# Printhead2.net
KiCad netlist of a schematic drawn in Altium Designer
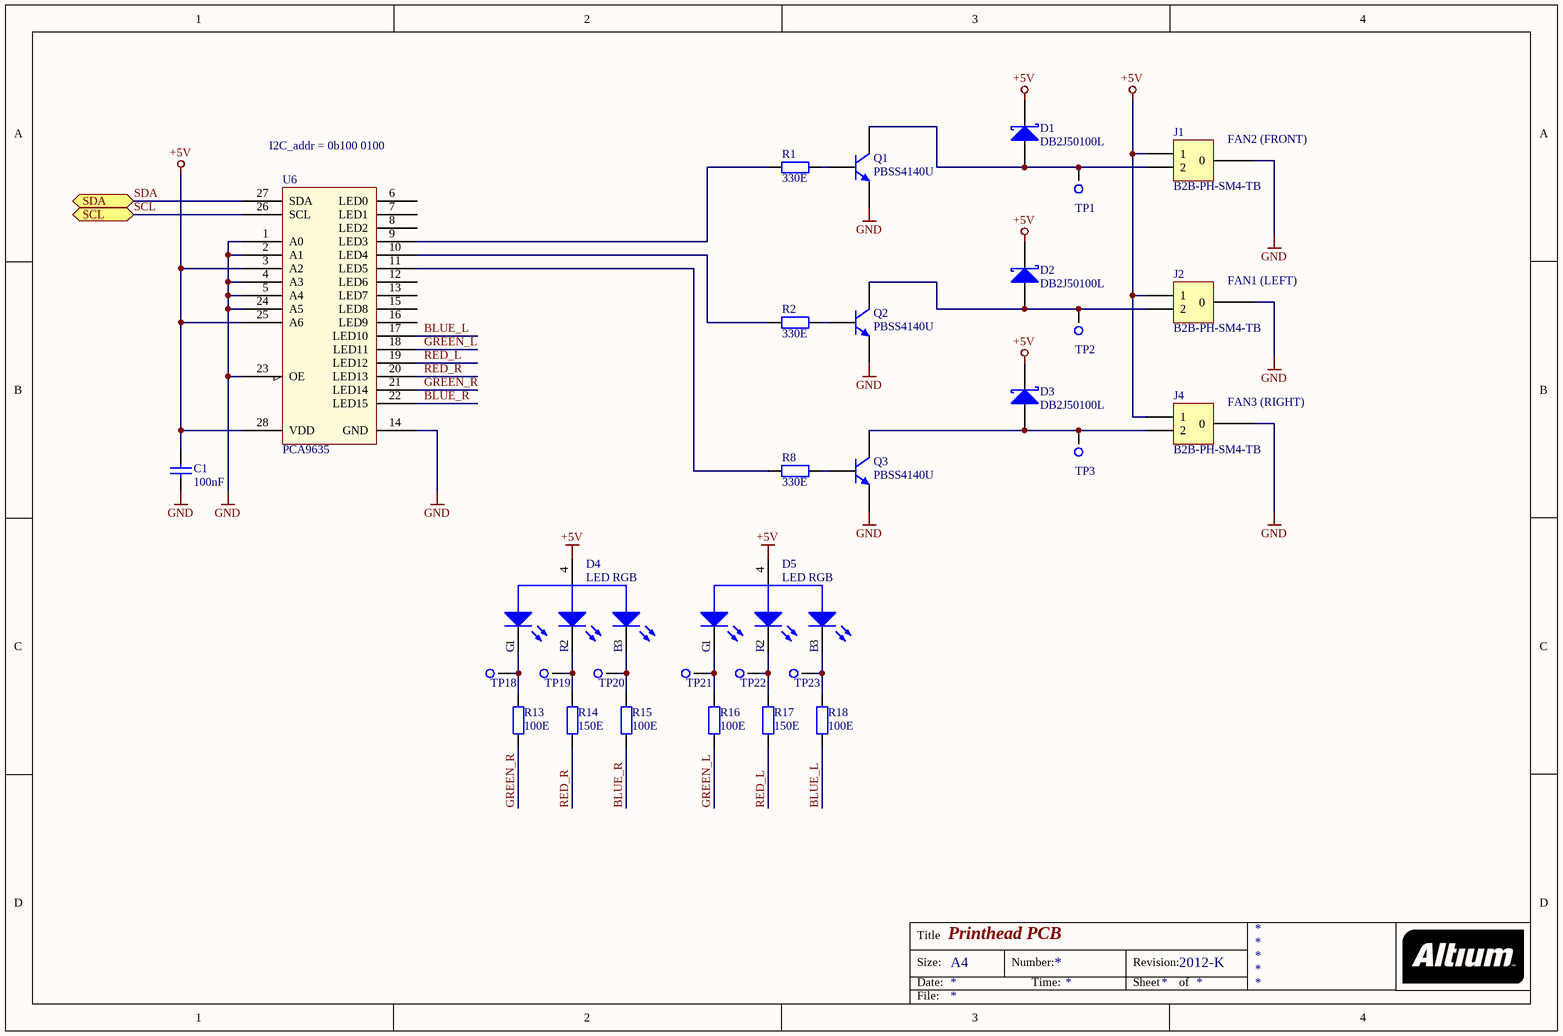
[diagram p0: Printhead2.SchDoc]

(export (version "E")
  (design (tool "Eeschema 10.0.6"))
  (components
    (comp (ref "C1")
      (value "100nF")
      (footprint "CAPC1608X09N")
      (description "CAP CER 0.1UF 50V 10% X7R 0603")
      (fields
        (field (name "MANUFACTURER") "Yageo")
        (field (name "MANUFACTURER PART NUMBER") "CC0603KRX7R9BB104")
      )
      (libsource (lib "Marlin") (part "100nF/50V/0603"))
    )
    (comp (ref "D1")
      (value "DB2J50100L")
      (footprint "SODFL2512X80N")
      (description "DIODE SCHOTTKY 50V 200MA MINI2")
      (fields (field (name "MANUFACTURER") "Panasonic Electronic Components - Semiconductor Products"))
      (libsource (lib "Marlin") (part "DB2J50100L"))
    )
    (comp (ref "D2")
      (value "DB2J50100L")
      (footprint "SODFL2512X80N")
      (description "DIODE SCHOTTKY 50V 200MA MINI2")
      (fields (field (name "MANUFACTURER") "Panasonic Electronic Components - Semiconductor Products"))
      (libsource (lib "Marlin") (part "DB2J50100L"))
    )
    (comp (ref "D3")
      (value "DB2J50100L")
      (footprint "SODFL2512X80N")
      (description "DIODE SCHOTTKY 50V 200MA MINI2")
      (fields (field (name "MANUFACTURER") "Panasonic Electronic Components - Semiconductor Products"))
      (libsource (lib "Marlin") (part "DB2J50100L"))
    )
    (comp (ref "D4")
      (value "LED RGB")
      (footprint "Dialight 598-8610-307F")
      (description "LED MULTICOLOR RED/GRN/BLUE")
      (fields (field (name "MFG") "Dialight") (field (name "MANUFACTURER PART NUMBER") "598-8610-307F"))
      (libsource (lib "Faber_SCH_lib") (part "LED 598-8810-307F"))
    )
    (comp (ref "D5")
      (value "LED RGB")
      (footprint "Dialight 598-8610-307F")
      (description "LED MULTICOLOR RED/GRN/BLUE")
      (fields (field (name "MFG") "Dialight") (field (name "MANUFACTURER PART NUMBER") "598-8610-307F"))
      (libsource (lib "Faber_SCH_lib") (part "LED 598-8810-307F"))
    )
    (comp (ref "J1")
      (value "B2B-PH-SM4-TB")
      (footprint "B2B-PH-SM4-TB")
      (description "JST B2B-PH-SM4-TB")
      (fields (field (name "MFG") "JST"))
      (libsource (lib "printehead") (part "Header 2"))
    )
    (comp (ref "J2")
      (value "B2B-PH-SM4-TB")
      (footprint "B2B-PH-SM4-TB")
      (description "JST B2B-PH-SM4-TB")
      (fields (field (name "MFG") "JST"))
      (libsource (lib "printehead") (part "Header 2"))
    )
    (comp (ref "J4")
      (value "B2B-PH-SM4-TB")
      (footprint "B2B-PH-SM4-TB")
      (description "JST B2B-PH-SM4-TB")
      (fields (field (name "MFG") "JST"))
      (libsource (lib "printehead") (part "Header 2"))
    )
    (comp (ref "Q1")
      (value "PBSS4140U")
      (footprint "SOT65P210X110-3N")
      (description "TRANS NPN 40V 1000MA SOT323")
      (fields
        (field (name "MANUFACTURER") "NXP Semiconductors")
        (field (name "MANUFACTURER PART NUMBER") "PBSS4140U,115")
      )
      (libsource (lib "Marlin") (part "PBSS4140U"))
    )
    (comp (ref "Q2")
      (value "PBSS4140U")
      (footprint "SOT65P210X110-3N")
      (description "TRANS NPN 40V 1000MA SOT323")
      (fields
        (field (name "MANUFACTURER") "NXP Semiconductors")
        (field (name "MANUFACTURER PART NUMBER") "PBSS4140U,115")
      )
      (libsource (lib "Marlin") (part "PBSS4140U"))
    )
    (comp (ref "Q3")
      (value "PBSS4140U")
      (footprint "SOT65P210X110-3N")
      (description "TRANS NPN 40V 1000MA SOT323")
      (fields
        (field (name "MANUFACTURER") "NXP Semiconductors")
        (field (name "MANUFACTURER PART NUMBER") "PBSS4140U,115")
      )
      (libsource (lib "Marlin") (part "PBSS4140U"))
    )
    (comp (ref "R1")
      (value "330E")
      (footprint "ulticontroller2:RESC1608X05N")
      (description "RES 330 OHM 1/10W 1% 0603 SMD")
      (fields
        (field (name "MANUFACTURER") "Vishay Dale")
        (field (name "MANUFACTURER PART NUMBER") "CRCW0603330RFKEA")
      )
      (libsource (lib "Marlin") (part "330E/0603"))
    )
    (comp (ref "R2")
      (value "330E")
      (footprint "RESC1608X05N")
      (description "RES 330 OHM 1/10W 1% 0603 SMD")
      (fields
        (field (name "MANUFACTURER") "Vishay Dale")
        (field (name "MANUFACTURER PART NUMBER") "CRCW0603330RFKEA")
      )
      (libsource (lib "Marlin") (part "330E/0603"))
    )
    (comp (ref "R8")
      (value "330E")
      (footprint "RESC1608X05N")
      (description "RES 330 OHM 1/10W 1% 0603 SMD")
      (fields
        (field (name "MANUFACTURER") "Vishay Dale")
        (field (name "MANUFACTURER PART NUMBER") "CRCW0603330RFKEA")
      )
      (libsource (lib "Marlin") (part "330E/0603"))
    )
    (comp (ref "R13")
      (value "100E")
      (footprint "R0805 (2012)")
      (description "Res 100E 0805 1% 125mW")
      (fields
        (field (name "MFG") "YAGEO")
        (field (name "MANUFACTURER PART NUMBER") "WRC31022/ RC0805FR-07100RL")
      )
      (libsource (lib "Faber_SCH_lib") (part "Res 100E 0805"))
    )
    (comp (ref "R14")
      (value "150E")
      (footprint "R0805 (2012)")
      (description "Res 150E 0805 1% 125mW")
      (fields (field (name "MFG") "YAGEO") (field (name "MANUFACTURER PART NUMBER") "2322 734 61501"))
      (libsource (lib "Faber_SCH_lib") (part "Res 150E 0805"))
    )
    (comp (ref "R15")
      (value "100E")
      (footprint "R0805 (2012)")
      (description "Res 100E 0805 1% 125mW")
      (fields
        (field (name "MFG") "YAGEO")
        (field (name "MANUFACTURER PART NUMBER") "WRC31022/ RC0805FR-07100RL")
      )
      (libsource (lib "Faber_SCH_lib") (part "Res 100E 0805"))
    )
    (comp (ref "R16")
      (value "100E")
      (footprint "R0805 (2012)")
      (description "Res 100E 0805 1% 125mW")
      (fields
        (field (name "MFG") "YAGEO")
        (field (name "MANUFACTURER PART NUMBER") "WRC31022/ RC0805FR-07100RL")
      )
      (libsource (lib "Faber_SCH_lib") (part "Res 100E 0805"))
    )
    (comp (ref "R17")
      (value "150E")
      (footprint "R0805 (2012)")
      (description "Res 150E 0805 1% 125mW")
      (fields (field (name "MFG") "YAGEO") (field (name "MANUFACTURER PART NUMBER") "2322 734 61501"))
      (libsource (lib "Faber_SCH_lib") (part "Res 150E 0805"))
    )
    (comp (ref "R18")
      (value "100E")
      (footprint "R0805 (2012)")
      (description "Res 100E 0805 1% 125mW")
      (fields
        (field (name "MFG") "YAGEO")
        (field (name "MANUFACTURER PART NUMBER") "WRC31022/ RC0805FR-07100RL")
      )
      (libsource (lib "Faber_SCH_lib") (part "Res 100E 0805"))
    )
    (comp (ref "TP1")
      (value "Testpoint 1.6mm")
      (footprint "Testpoint 1.6mm")
      (libsource (lib "Ultimaker") (part "Testpoint 1.6mm"))
    )
    (comp (ref "TP2")
      (value "Testpoint 1.6mm")
      (footprint "Testpoint 1.6mm")
      (libsource (lib "Ultimaker") (part "Testpoint 1.6mm"))
    )
    (comp (ref "TP3")
      (value "Testpoint 1.6mm")
      (footprint "Testpoint 1.6mm")
      (libsource (lib "Ultimaker") (part "Testpoint 1.6mm"))
    )
    (comp (ref "TP18")
      (value "Testpoint 1.6mm")
      (footprint "Testpoint 1.6mm")
      (libsource (lib "Ultimaker") (part "Testpoint 1.6mm"))
    )
    (comp (ref "TP19")
      (value "Testpoint 1.6mm")
      (footprint "Testpoint 1.6mm")
      (libsource (lib "Ultimaker") (part "Testpoint 1.6mm"))
    )
    (comp (ref "TP20")
      (value "Testpoint 1.6mm")
      (footprint "Testpoint 1.6mm")
      (libsource (lib "Ultimaker") (part "Testpoint 1.6mm"))
    )
    (comp (ref "TP21")
      (value "Testpoint 1.6mm")
      (footprint "Testpoint 1.6mm")
      (libsource (lib "Ultimaker") (part "Testpoint 1.6mm"))
    )
    (comp (ref "TP22")
      (value "Testpoint 1.6mm")
      (footprint "Testpoint 1.6mm")
      (libsource (lib "Ultimaker") (part "Testpoint 1.6mm"))
    )
    (comp (ref "TP23")
      (value "Testpoint 1.6mm")
      (footprint "Testpoint 1.6mm")
      (libsource (lib "Ultimaker") (part "Testpoint 1.6mm"))
    )
    (comp (ref "U6")
      (value "PCA9635")
      (footprint "TSOP65P640X110-28N")
      (description "16-bit Fm+ I2C-bus LED driver")
      (fields (field (name "MFG") "NXP") (field (name "MANUFACTURER PART NUMBER") "PCA9635PW"))
      (libsource (lib "printehead") (part "PCA9635"))
    )
  )
  (nets
    (net (code "1") (name "+5V") (class "Default")
      (node (ref "C1") (pin "2") (pinfunction "2_2") (pintype "passive"))
      (node (ref "D1") (pin "1") (pinfunction "K_1") (pintype "passive"))
      (node (ref "D2") (pin "1") (pinfunction "K_1") (pintype "passive"))
      (node (ref "D3") (pin "1") (pinfunction "K_1") (pintype "passive"))
      (node (ref "D4") (pin "4") (pinfunction "4_4") (pintype "passive"))
      (node (ref "D5") (pin "4") (pinfunction "4_4") (pintype "passive"))
      (node (ref "J1") (pin "1") (pinfunction "1_1") (pintype "passive"))
      (node (ref "J2") (pin "1") (pinfunction "1_1") (pintype "passive"))
      (node (ref "J4") (pin "1") (pinfunction "1_1") (pintype "passive"))
      (node (ref "U6") (pin "25") (pinfunction "A6_25") (pintype "passive"))
      (node (ref "U6") (pin "28") (pinfunction "VDD_28") (pintype "power_in"))
      (node (ref "U6") (pin "3") (pinfunction "A2_3") (pintype "passive"))
    )
    (net (code "2") (name "/BLUE_L") (class "Default")
      (node (ref "R18") (pin "1") (pinfunction "1_1") (pintype "passive"))
      (node (ref "U6") (pin "17") (pinfunction "LED10_17") (pintype "passive"))
    )
    (net (code "3") (name "/BLUE_R") (class "Default")
      (node (ref "R15") (pin "1") (pinfunction "1_1") (pintype "passive"))
      (node (ref "U6") (pin "22") (pinfunction "LED15_22") (pintype "passive"))
    )
    (net (code "4") (name "/GREEN_L") (class "Default")
      (node (ref "R16") (pin "1") (pinfunction "1_1") (pintype "passive"))
      (node (ref "U6") (pin "18") (pinfunction "LED11_18") (pintype "passive"))
    )
    (net (code "5") (name "/GREEN_R") (class "Default")
      (node (ref "R13") (pin "1") (pinfunction "1_1") (pintype "passive"))
      (node (ref "U6") (pin "21") (pinfunction "LED14_21") (pintype "passive"))
    )
    (net (code "6") (name "/RED_L") (class "Default")
      (node (ref "R17") (pin "1") (pinfunction "1_1") (pintype "passive"))
      (node (ref "U6") (pin "19") (pinfunction "LED12_19") (pintype "passive"))
    )
    (net (code "7") (name "/RED_R") (class "Default")
      (node (ref "R14") (pin "1") (pinfunction "1_1") (pintype "passive"))
      (node (ref "U6") (pin "20") (pinfunction "LED13_20") (pintype "passive"))
    )
    (net (code "8") (name "/SCL") (class "Default")
      (node (ref "U6") (pin "26") (pinfunction "SCL_26") (pintype "passive"))
    )
    (net (code "9") (name "/SDA") (class "Default")
      (node (ref "U6") (pin "27") (pinfunction "SDA_27") (pintype "passive"))
    )
    (net (code "10") (name "GND") (class "Default")
      (node (ref "C1") (pin "1") (pinfunction "1_1") (pintype "passive"))
      (node (ref "J1") (pin "0") (pinfunction "0_0") (pintype "power_in"))
      (node (ref "J2") (pin "0") (pinfunction "0_0") (pintype "power_in"))
      (node (ref "J4") (pin "0") (pinfunction "0_0") (pintype "power_in"))
      (node (ref "Q1") (pin "2") (pinfunction "E_2") (pintype "passive"))
      (node (ref "Q2") (pin "2") (pinfunction "E_2") (pintype "passive"))
      (node (ref "Q3") (pin "2") (pinfunction "E_2") (pintype "passive"))
      (node (ref "U6") (pin "1") (pinfunction "A0_1") (pintype "passive"))
      (node (ref "U6") (pin "14") (pinfunction "GND_14") (pintype "power_in"))
      (node (ref "U6") (pin "2") (pinfunction "A1_2") (pintype "passive"))
      (node (ref "U6") (pin "23") (pinfunction "OE_23") (pintype "passive"))
      (node (ref "U6") (pin "24") (pinfunction "A5_24") (pintype "passive"))
      (node (ref "U6") (pin "4") (pinfunction "A3_4") (pintype "passive"))
      (node (ref "U6") (pin "5") (pinfunction "A4_5") (pintype "passive"))
    )
    (net (code "11") (name "Net-(D1-A)") (class "Default")
      (node (ref "D1") (pin "2") (pinfunction "A_2") (pintype "passive"))
      (node (ref "J1") (pin "2") (pinfunction "2_2") (pintype "passive"))
      (node (ref "Q1") (pin "3") (pinfunction "C_3") (pintype "passive"))
      (node (ref "TP1") (pin "1") (pinfunction "1_1") (pintype "passive"))
    )
    (net (code "12") (name "Net-(D2-A)") (class "Default")
      (node (ref "D2") (pin "2") (pinfunction "A_2") (pintype "passive"))
      (node (ref "J2") (pin "2") (pinfunction "2_2") (pintype "passive"))
      (node (ref "Q2") (pin "3") (pinfunction "C_3") (pintype "passive"))
      (node (ref "TP2") (pin "1") (pinfunction "1_1") (pintype "passive"))
    )
    (net (code "13") (name "Net-(D3-A)") (class "Default")
      (node (ref "D3") (pin "2") (pinfunction "A_2") (pintype "passive"))
      (node (ref "J4") (pin "2") (pinfunction "2_2") (pintype "passive"))
      (node (ref "Q3") (pin "3") (pinfunction "C_3") (pintype "passive"))
      (node (ref "TP3") (pin "1") (pinfunction "1_1") (pintype "passive"))
    )
    (net (code "14") (name "Net-(D4-Pad1)") (class "Default")
      (node (ref "D4") (pin "1") (pinfunction "1_1") (pintype "passive"))
      (node (ref "R13") (pin "2") (pinfunction "2_2") (pintype "passive"))
      (node (ref "TP18") (pin "1") (pinfunction "1_1") (pintype "passive"))
    )
    (net (code "15") (name "Net-(D4-Pad2)") (class "Default")
      (node (ref "D4") (pin "2") (pinfunction "2_2") (pintype "passive"))
      (node (ref "R14") (pin "2") (pinfunction "2_2") (pintype "passive"))
      (node (ref "TP19") (pin "1") (pinfunction "1_1") (pintype "passive"))
    )
    (net (code "16") (name "Net-(D4-Pad3)") (class "Default")
      (node (ref "D4") (pin "3") (pinfunction "3_3") (pintype "passive"))
      (node (ref "R15") (pin "2") (pinfunction "2_2") (pintype "passive"))
      (node (ref "TP20") (pin "1") (pinfunction "1_1") (pintype "passive"))
    )
    (net (code "17") (name "Net-(D5-Pad1)") (class "Default")
      (node (ref "D5") (pin "1") (pinfunction "1_1") (pintype "passive"))
      (node (ref "R16") (pin "2") (pinfunction "2_2") (pintype "passive"))
      (node (ref "TP21") (pin "1") (pinfunction "1_1") (pintype "passive"))
    )
    (net (code "18") (name "Net-(D5-Pad2)") (class "Default")
      (node (ref "D5") (pin "2") (pinfunction "2_2") (pintype "passive"))
      (node (ref "R17") (pin "2") (pinfunction "2_2") (pintype "passive"))
      (node (ref "TP22") (pin "1") (pinfunction "1_1") (pintype "passive"))
    )
    (net (code "19") (name "Net-(D5-Pad3)") (class "Default")
      (node (ref "D5") (pin "3") (pinfunction "3_3") (pintype "passive"))
      (node (ref "R18") (pin "2") (pinfunction "2_2") (pintype "passive"))
      (node (ref "TP23") (pin "1") (pinfunction "1_1") (pintype "passive"))
    )
    (net (code "20") (name "Net-(Q1-B)") (class "Default")
      (node (ref "Q1") (pin "1") (pinfunction "B_1") (pintype "passive"))
      (node (ref "R1") (pin "2") (pinfunction "2_2") (pintype "passive"))
    )
    (net (code "21") (name "Net-(Q2-B)") (class "Default")
      (node (ref "Q2") (pin "1") (pinfunction "B_1") (pintype "passive"))
      (node (ref "R2") (pin "2") (pinfunction "2_2") (pintype "passive"))
    )
    (net (code "22") (name "Net-(Q3-B)") (class "Default")
      (node (ref "Q3") (pin "1") (pinfunction "B_1") (pintype "passive"))
      (node (ref "R8") (pin "2") (pinfunction "2_2") (pintype "passive"))
    )
    (net (code "23") (name "Net-(U6-LED3)") (class "Default")
      (node (ref "R1") (pin "1") (pinfunction "1_1") (pintype "passive"))
      (node (ref "U6") (pin "9") (pinfunction "LED3_9") (pintype "passive"))
    )
    (net (code "24") (name "Net-(U6-LED4)") (class "Default")
      (node (ref "R2") (pin "1") (pinfunction "1_1") (pintype "passive"))
      (node (ref "U6") (pin "10") (pinfunction "LED4_10") (pintype "passive"))
    )
    (net (code "25") (name "Net-(U6-LED5)") (class "Default")
      (node (ref "R8") (pin "1") (pinfunction "1_1") (pintype "passive"))
      (node (ref "U6") (pin "11") (pinfunction "LED5_11") (pintype "passive"))
    )
    (net (code "26") (name "unconnected-(U6-LED0-Pad6)") (class "Default")
      (node (ref "U6") (pin "6") (pinfunction "LED0_6") (pintype "passive"))
    )
    (net (code "27") (name "unconnected-(U6-LED1-Pad7)") (class "Default")
      (node (ref "U6") (pin "7") (pinfunction "LED1_7") (pintype "passive"))
    )
    (net (code "28") (name "unconnected-(U6-LED2-Pad8)") (class "Default")
      (node (ref "U6") (pin "8") (pinfunction "LED2_8") (pintype "passive"))
    )
    (net (code "29") (name "unconnected-(U6-LED6-Pad12)") (class "Default")
      (node (ref "U6") (pin "12") (pinfunction "LED6_12") (pintype "passive"))
    )
    (net (code "30") (name "unconnected-(U6-LED7-Pad13)") (class "Default")
      (node (ref "U6") (pin "13") (pinfunction "LED7_13") (pintype "passive"))
    )
    (net (code "31") (name "unconnected-(U6-LED8-Pad15)") (class "Default")
      (node (ref "U6") (pin "15") (pinfunction "LED8_15") (pintype "passive"))
    )
    (net (code "32") (name "unconnected-(U6-LED9-Pad16)") (class "Default")
      (node (ref "U6") (pin "16") (pinfunction "LED9_16") (pintype "passive"))
    )
  )
)
